# ProPrj_stm32G474_PPO_Display_2026-02-25.net
KiCad netlist of a schematic drawn in EasyEDA Pro
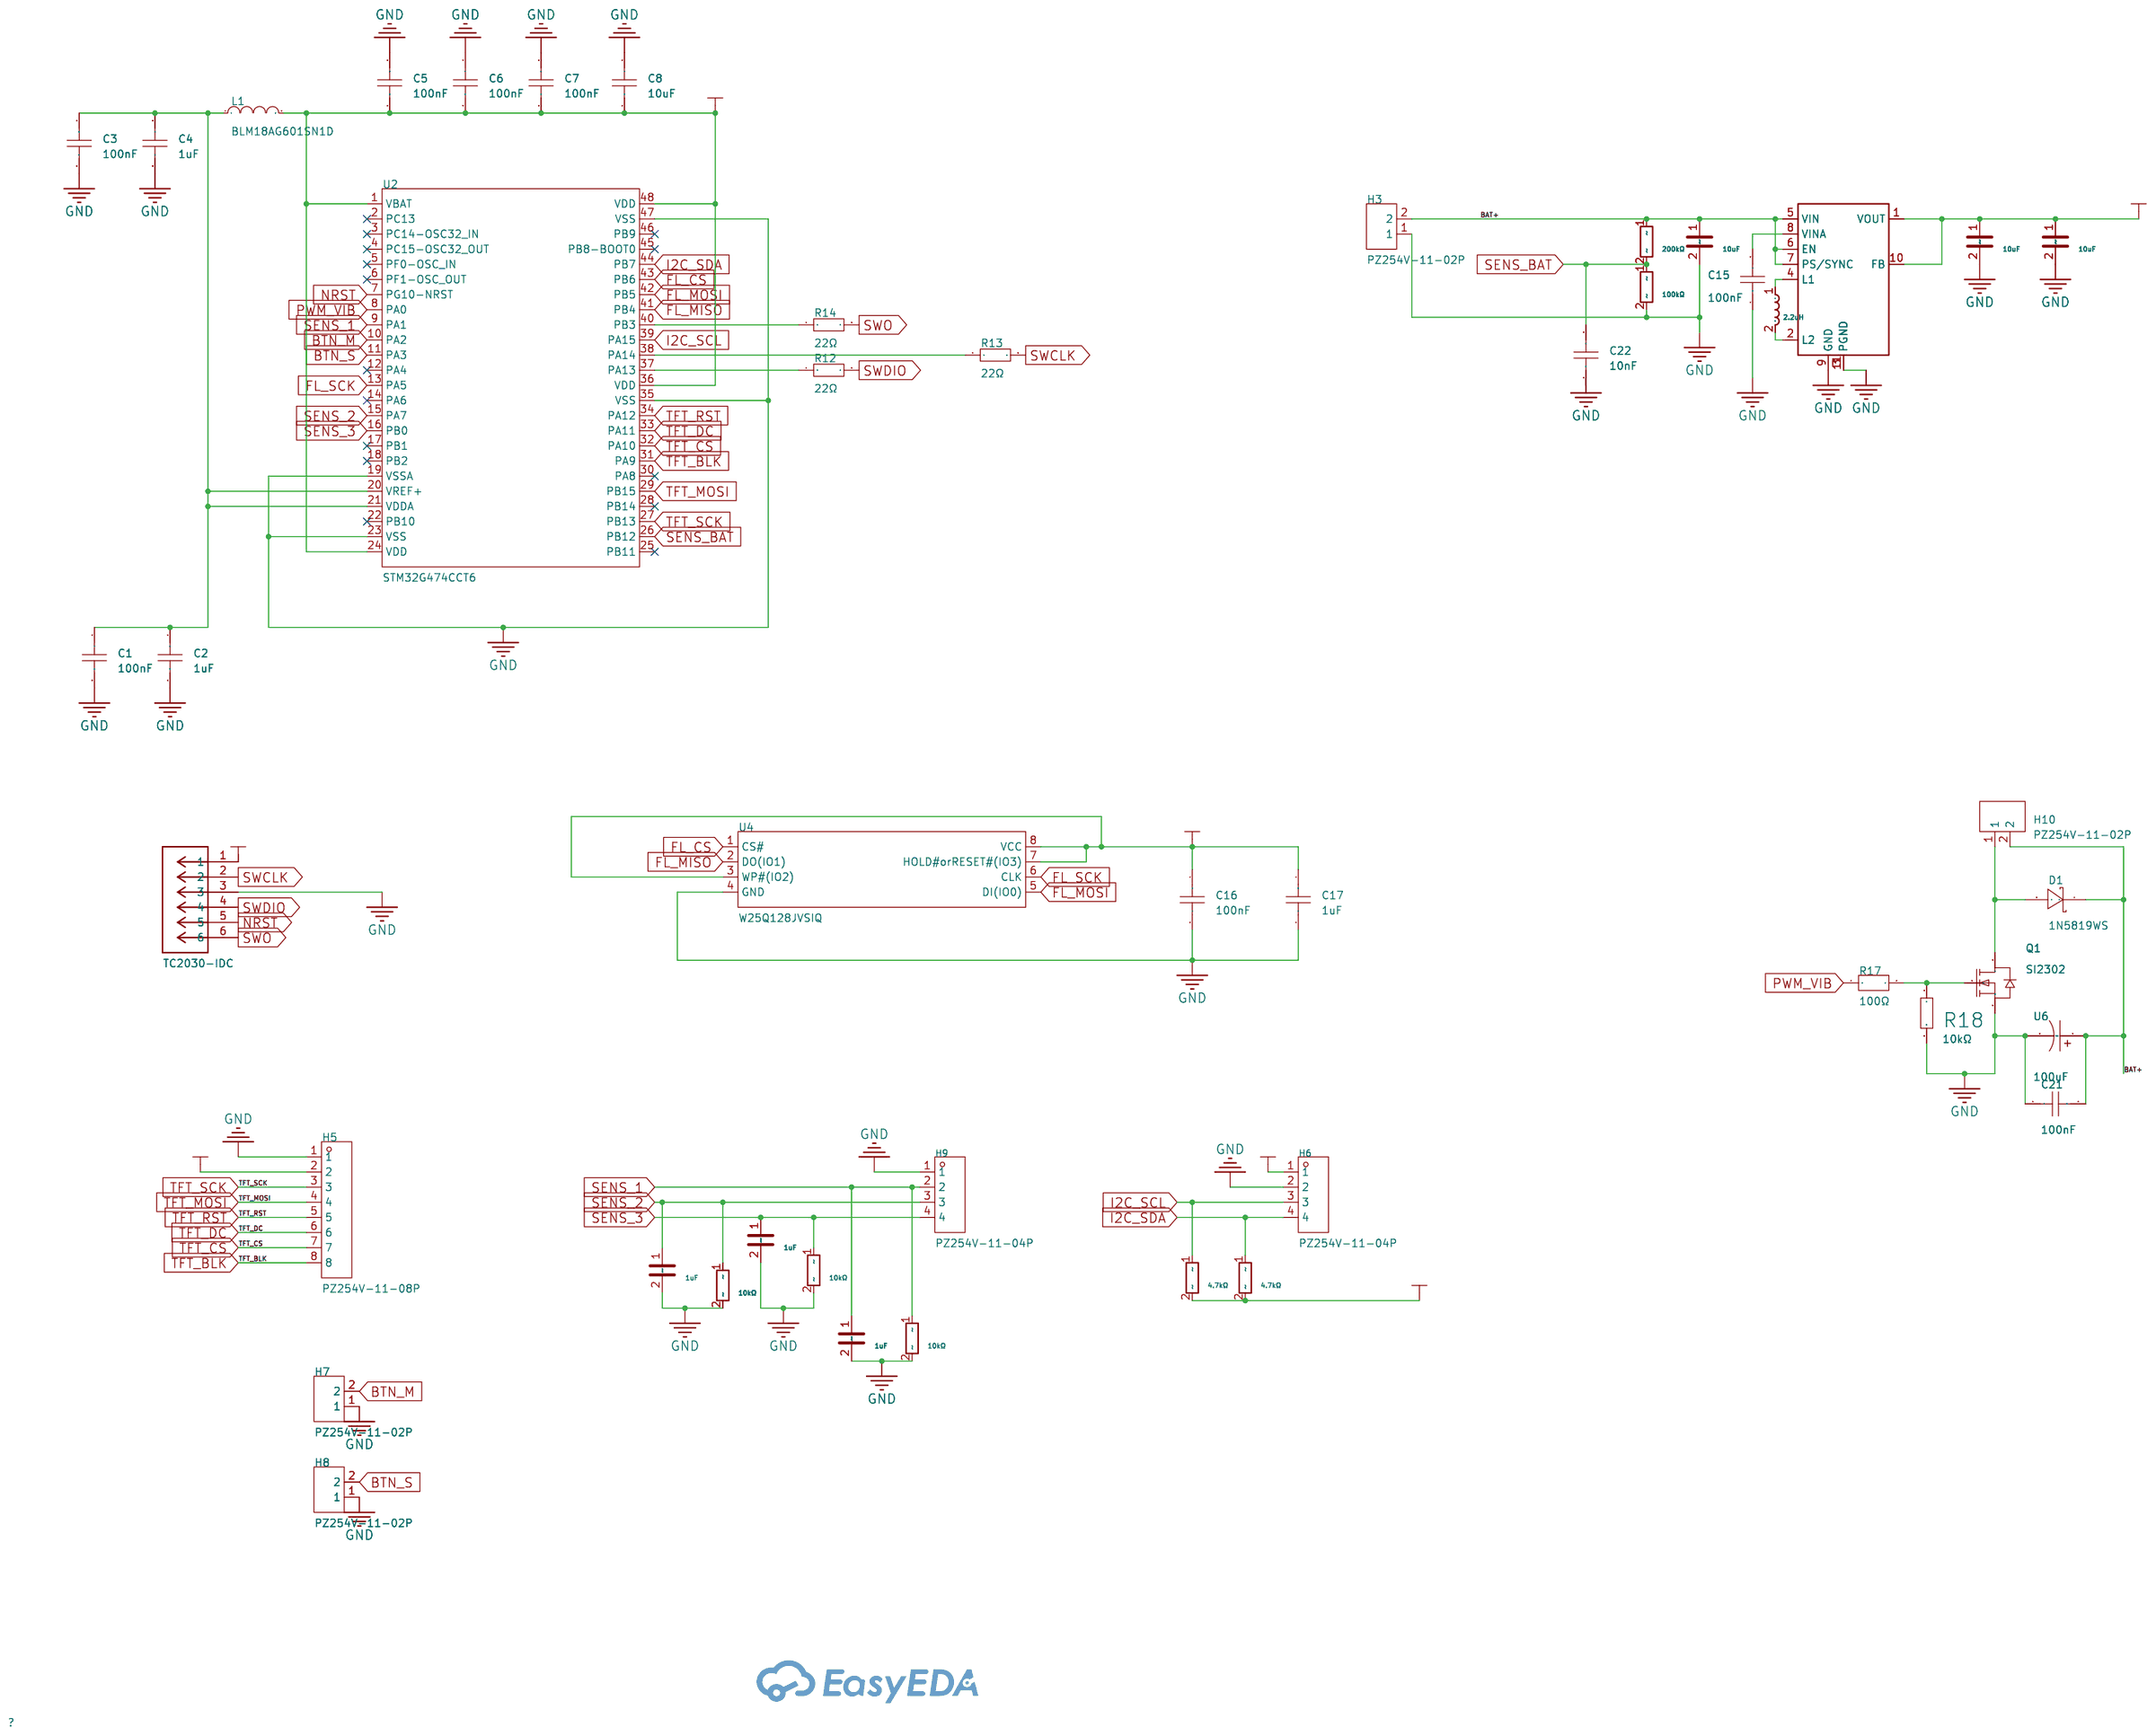
[diagram p0: schematic sheet]

(export (version "E")
  (design (tool "Eeschema 10.0.6"))
  (components
    (comp (ref "C1")
      (value "100nF")
      (footprint "easyedapro:C0603")
      (description "Capacitance:100nF Tolerance:±10% Tolerance:±10% Voltage Rating:50V Temperature Coefficient:X7R")
      (fields
        (field (name "Manufacturer Part") "CC0603KRX7R9BB104")
        (field (name "Manufacturer") "YAGEO(国巨)")
      )
      (libsource (lib "easyedapro") (part "CC0603KRX7R9BB104"))
    )
    (comp (ref "C2")
      (value "1uF")
      (footprint "easyedapro:C0603")
      (description "Capacitance:1uF Tolerance:±10% Tolerance:±10% Voltage Rating:50V Temperature Coefficient:X5R")
      (fields
        (field (name "Manufacturer Part") "CL10A105KB8NNNC")
        (field (name "Manufacturer") "SAMSUNG(三星)")
      )
      (libsource (lib "easyedapro") (part "CL10A105KB8NNNC"))
    )
    (comp (ref "C3")
      (value "100nF")
      (footprint "easyedapro:C0603")
      (description "Capacitance:100nF Tolerance:±10% Tolerance:±10% Voltage Rating:50V Temperature Coefficient:X7R")
      (fields
        (field (name "Manufacturer Part") "CC0603KRX7R9BB104")
        (field (name "Manufacturer") "YAGEO(国巨)")
      )
      (libsource (lib "easyedapro") (part "CC0603KRX7R9BB104"))
    )
    (comp (ref "C4")
      (value "1uF")
      (footprint "easyedapro:C0603")
      (description "Capacitance:1uF Tolerance:±10% Tolerance:±10% Voltage Rating:50V Temperature Coefficient:X5R")
      (fields
        (field (name "Manufacturer Part") "CL10A105KB8NNNC")
        (field (name "Manufacturer") "SAMSUNG(三星)")
      )
      (libsource (lib "easyedapro") (part "CL10A105KB8NNNC"))
    )
    (comp (ref "C5")
      (value "100nF")
      (footprint "easyedapro:C0603")
      (description "Capacitance:100nF Tolerance:±10% Tolerance:±10% Voltage Rating:50V Temperature Coefficient:X7R")
      (fields
        (field (name "Manufacturer Part") "CC0603KRX7R9BB104")
        (field (name "Manufacturer") "YAGEO(国巨)")
      )
      (libsource (lib "easyedapro") (part "CC0603KRX7R9BB104"))
    )
    (comp (ref "C6")
      (value "100nF")
      (footprint "easyedapro:C0603")
      (description "Capacitance:100nF Tolerance:±10% Tolerance:±10% Voltage Rating:50V Temperature Coefficient:X7R")
      (fields
        (field (name "Manufacturer Part") "CC0603KRX7R9BB104")
        (field (name "Manufacturer") "YAGEO(国巨)")
      )
      (libsource (lib "easyedapro") (part "CC0603KRX7R9BB104"))
    )
    (comp (ref "C7")
      (value "100nF")
      (footprint "easyedapro:C0603")
      (description "Capacitance:100nF Tolerance:±10% Tolerance:±10% Voltage Rating:50V Temperature Coefficient:X7R")
      (fields
        (field (name "Manufacturer Part") "CC0603KRX7R9BB104")
        (field (name "Manufacturer") "YAGEO(国巨)")
      )
      (libsource (lib "easyedapro") (part "CC0603KRX7R9BB104"))
    )
    (comp (ref "C8")
      (value "10uF")
      (footprint "easyedapro:C0603")
      (description "Capacitance:10uF Tolerance:±20% Tolerance:±20% Voltage Rating:6.3V Temperature Coefficient:X5R")
      (fields
        (field (name "Manufacturer Part") "CL10A106MQ8NNNC")
        (field (name "Manufacturer") "SAMSUNG(三星)")
      )
      (libsource (lib "easyedapro") (part "CL10A106MQ8NNNC"))
    )
    (comp (ref "C9")
      (value "1uF")
      (footprint "easyedapro:Capacitor_SMD:C_0603_1608Metric")
      (description "Capacitance:1uF Tolerance:±10% Tolerance:±10% Voltage Rating:50V Temperature Coefficient:X7R")
      (fields
        (field (name "Manufacturer Part") "CL10B105KB8NQNC")
        (field (name "Manufacturer") "SAMSUNG(三星)")
      )
      (libsource (lib "easyedapro") (part "Device_C"))
    )
    (comp (ref "C10")
      (value "10uF")
      (footprint "easyedapro:Capacitor_SMD:C_0603_1608Metric")
      (description "Capacitance:10uF Tolerance:±20% Tolerance:±20% Voltage Rating:6.3V Temperature Coefficient:X5R")
      (fields
        (field (name "Manufacturer Part") "CL10A106MQ8NNNC")
        (field (name "Manufacturer") "SAMSUNG(三星)")
      )
      (libsource (lib "easyedapro") (part "Device_C"))
    )
    (comp (ref "C11")
      (value "10uF")
      (footprint "easyedapro:Capacitor_SMD:C_0603_1608Metric")
      (description "Capacitance:10uF Tolerance:±20% Tolerance:±20% Voltage Rating:25V Temperature Coefficient:X5R")
      (fields
        (field (name "Manufacturer Part") "CL10A106MA8NRNC")
        (field (name "Manufacturer") "SAMSUNG(三星)")
      )
      (libsource (lib "easyedapro") (part "Device_C"))
    )
    (comp (ref "C15")
      (value "100nF")
      (footprint "easyedapro:C0603")
      (description "Capacitance:100nF Tolerance:±10% Tolerance:±10% Voltage Rating:50V Temperature Coefficient:X7R")
      (fields
        (field (name "Manufacturer Part") "CC0603KRX7R9BB104")
        (field (name "Manufacturer") "YAGEO(国巨)")
      )
      (libsource (lib "easyedapro") (part "CC0603KRX7R9BB104"))
    )
    (comp (ref "C16")
      (value "100nF")
      (footprint "easyedapro:C0603")
      (description "Capacitance:100nF Tolerance:±10% Tolerance:±10% Voltage Rating:50V Temperature Coefficient:X7R")
      (fields
        (field (name "Manufacturer Part") "CC0603KRX7R9BB104")
        (field (name "Manufacturer") "YAGEO(国巨)")
      )
      (libsource (lib "easyedapro") (part "CC0603KRX7R9BB104"))
    )
    (comp (ref "C17")
      (value "1uF")
      (footprint "easyedapro:C0603")
      (description "Capacitance:1uF Tolerance:±10% Tolerance:±10% Voltage Rating:50V Temperature Coefficient:X5R")
      (fields
        (field (name "Manufacturer Part") "CL10A105KB8NNNC")
        (field (name "Manufacturer") "SAMSUNG(三星)")
      )
      (libsource (lib "easyedapro") (part "CL10A105KB8NNNC"))
    )
    (comp (ref "C18")
      (value "10uF")
      (footprint "easyedapro:Capacitor_SMD:C_0603_1608Metric")
      (description "Capacitance:10uF Tolerance:±20% Tolerance:±20% Voltage Rating:25V Temperature Coefficient:X5R")
      (fields
        (field (name "Manufacturer Part") "CL10A106MA8NRNC")
        (field (name "Manufacturer") "SAMSUNG(三星)")
      )
      (libsource (lib "easyedapro") (part "Device_C"))
    )
    (comp (ref "C19")
      (value "1uF")
      (footprint "easyedapro:Capacitor_SMD:C_0603_1608Metric")
      (description "Capacitance:1uF Tolerance:±10% Tolerance:±10% Voltage Rating:50V Temperature Coefficient:X7R")
      (fields
        (field (name "Manufacturer Part") "CL10B105KB8NQNC")
        (field (name "Manufacturer") "SAMSUNG(三星)")
      )
      (libsource (lib "easyedapro") (part "Device_C"))
    )
    (comp (ref "C20")
      (value "1uF")
      (footprint "easyedapro:Capacitor_SMD:C_0603_1608Metric")
      (description "Capacitance:1uF Tolerance:±10% Tolerance:±10% Voltage Rating:50V Temperature Coefficient:X7R")
      (fields
        (field (name "Manufacturer Part") "CL10B105KB8NQNC")
        (field (name "Manufacturer") "SAMSUNG(三星)")
      )
      (libsource (lib "easyedapro") (part "Device_C"))
    )
    (comp (ref "C21")
      (value "100nF")
      (footprint "easyedapro:C0603")
      (description "Capacitance:100nF Tolerance:±10% Tolerance:±10% Voltage Rating:50V Temperature Coefficient:X7R")
      (fields
        (field (name "Manufacturer Part") "CC0603KRX7R9BB104")
        (field (name "Manufacturer") "YAGEO(国巨)")
      )
      (libsource (lib "easyedapro") (part "CC0603KRX7R9BB104"))
    )
    (comp (ref "C22")
      (value "10nF")
      (footprint "easyedapro:C0603")
      (description "Capacitance:10nF Tolerance:±10% Tolerance:±10% Voltage Rating:50V Temperature Coefficient:X7R")
      (fields
        (field (name "Manufacturer Part") "CL10B103KB8NNNC")
        (field (name "Manufacturer") "SAMSUNG(三星)")
      )
      (libsource (lib "easyedapro") (part "CC0603KRX7R9BB104"))
    )
    (comp (ref "D1")
      (value "1N5819WS")
      (footprint "easyedapro:SOD-323_L1.8-W1.3-LS2.5-RD")
      (fields (field (name "Manufacturer") "Hottech(合科泰)"))
      (libsource (lib "easyedapro") (part "1N5819WS"))
    )
    (comp (ref "H3")
      (value "PZ254V-11-02P")
      (footprint "easyedapro:HDR-TH_2P-P2.54-V-M")
      (fields (field (name "Manufacturer") "XFCN(兴飞)"))
      (libsource (lib "easyedapro") (part "PZ254V-11-02P"))
    )
    (comp (ref "H5")
      (value "PZ254V-11-08P")
      (footprint "easyedapro:HDR-TH_8P-P2.54-V-M")
      (fields (field (name "Manufacturer") "XFCN(兴飞)"))
      (libsource (lib "easyedapro") (part "PZ254V-11-08P"))
    )
    (comp (ref "H6")
      (value "PZ254V-11-04P")
      (footprint "easyedapro:HDR-TH_4P-P2.54-V-M")
      (fields (field (name "Manufacturer") "XFCN(兴飞)"))
      (libsource (lib "easyedapro") (part "PZ254V-11-04P_C2691448"))
    )
    (comp (ref "H7")
      (value "PZ254V-11-02P")
      (footprint "easyedapro:HDR-TH_2P-P2.54-V-M")
      (fields (field (name "Manufacturer") "XFCN(兴飞)"))
      (libsource (lib "easyedapro") (part "PZ254V-11-02P"))
    )
    (comp (ref "H8")
      (value "PZ254V-11-02P")
      (footprint "easyedapro:HDR-TH_2P-P2.54-V-M")
      (fields (field (name "Manufacturer") "XFCN(兴飞)"))
      (libsource (lib "easyedapro") (part "PZ254V-11-02P"))
    )
    (comp (ref "H9")
      (value "PZ254V-11-04P")
      (footprint "easyedapro:HDR-TH_4P-P2.54-V-M")
      (fields (field (name "Manufacturer") "XFCN(兴飞)"))
      (libsource (lib "easyedapro") (part "PZ254V-11-04P_C2691448"))
    )
    (comp (ref "H10")
      (value "PZ254V-11-02P")
      (footprint "easyedapro:HDR-TH_2P-P2.54-V-M")
      (fields (field (name "Manufacturer") "XFCN(兴飞)"))
      (libsource (lib "easyedapro") (part "PZ254V-11-02P"))
    )
    (comp (ref "L1")
      (value "BLM18AG601SN1D")
      (footprint "easyedapro:L0603")
      (fields (field (name "Manufacturer") "muRata(村田)"))
      (libsource (lib "easyedapro") (part "BLM18AG601SN1D"))
    )
    (comp (ref "L2")
      (value "2.2uH")
      (footprint "easyedapro:Inductor_SMD:L_0402_1005Metric")
      (fields (field (name "Manufacturer Part") "LQH3NPN2R2MMEL") (field (name "Manufacturer") "muRata(村田)"))
      (libsource (lib "easyedapro") (part "Device_L"))
    )
    (comp (ref "Q1")
      (value "SI2302")
      (footprint "easyedapro:SOT-23-3_L2.9-W1.3-P1.90-LS2.4-BR")
      (fields (field (name "Manufacturer") "FOSAN(富捷/富信)"))
      (libsource (lib "easyedapro") (part "SI2302_C20628873"))
    )
    (comp (ref "R7")
      (value "200kΩ")
      (footprint "easyedapro:Resistor_SMD:R_0201_0603Metric")
      (fields
        (field (name "Manufacturer Part") "0603WAF2003T5E")
        (field (name "Manufacturer") "UNI-ROYAL(厚声)")
      )
      (libsource (lib "easyedapro") (part "Device_R"))
    )
    (comp (ref "R8")
      (value "100kΩ")
      (footprint "easyedapro:Resistor_SMD:R_0201_0603Metric")
      (fields (field (name "Manufacturer Part") "FRC0603J104 TS") (field (name "Manufacturer") "FOJAN(富捷)"))
      (libsource (lib "easyedapro") (part "Device_R"))
    )
    (comp (ref "R11")
      (value "10kΩ")
      (footprint "easyedapro:Resistor_SMD:R_0201_0603Metric")
      (fields
        (field (name "Manufacturer Part") "0603WAF1002T5E")
        (field (name "Manufacturer") "UNI-ROYAL(厚声)")
      )
      (libsource (lib "easyedapro") (part "Device_R"))
    )
    (comp (ref "R12")
      (value "22Ω")
      (footprint "easyedapro:R0603")
      (fields
        (field (name "Manufacturer Part") "0603WAF220JT5E")
        (field (name "Manufacturer") "UNI-ROYAL(厚声)")
      )
      (libsource (lib "easyedapro") (part "0603WAF220JT5E"))
    )
    (comp (ref "R13")
      (value "22Ω")
      (footprint "easyedapro:R0603")
      (fields
        (field (name "Manufacturer Part") "0603WAF220JT5E")
        (field (name "Manufacturer") "UNI-ROYAL(厚声)")
      )
      (libsource (lib "easyedapro") (part "0603WAF220JT5E"))
    )
    (comp (ref "R14")
      (value "22Ω")
      (footprint "easyedapro:R0603")
      (fields
        (field (name "Manufacturer Part") "0603WAF220JT5E")
        (field (name "Manufacturer") "UNI-ROYAL(厚声)")
      )
      (libsource (lib "easyedapro") (part "0603WAF220JT5E"))
    )
    (comp (ref "R15")
      (value "10kΩ")
      (footprint "easyedapro:Resistor_SMD:R_0201_0603Metric")
      (fields
        (field (name "Manufacturer Part") "0603WAF1002T5E")
        (field (name "Manufacturer") "UNI-ROYAL(厚声)")
      )
      (libsource (lib "easyedapro") (part "Device_R"))
    )
    (comp (ref "R16")
      (value "10kΩ")
      (footprint "easyedapro:Resistor_SMD:R_0201_0603Metric")
      (fields
        (field (name "Manufacturer Part") "0603WAF1002T5E")
        (field (name "Manufacturer") "UNI-ROYAL(厚声)")
      )
      (libsource (lib "easyedapro") (part "Device_R"))
    )
    (comp (ref "R17")
      (value "100Ω")
      (footprint "easyedapro:R0603")
      (fields (field (name "Manufacturer Part") "FRC0603J101 TS") (field (name "Manufacturer") "FOJAN(富捷)"))
      (libsource (lib "easyedapro") (part "FRC0603J101 TS"))
    )
    (comp (ref "R18")
      (value "10kΩ")
      (footprint "easyedapro:R0603")
      (fields
        (field (name "Manufacturer Part") "0603WAF1002T5E")
        (field (name "Manufacturer") "UNI-ROYAL(厚声)")
      )
      (libsource (lib "easyedapro") (part "0603WAF1002T5E"))
    )
    (comp (ref "R19")
      (value "4.7kΩ")
      (footprint "easyedapro:Resistor_SMD:R_0201_0603Metric")
      (fields
        (field (name "Manufacturer Part") "0603WAF4701T5E")
        (field (name "Manufacturer") "UNI-ROYAL(厚声)")
      )
      (libsource (lib "easyedapro") (part "Device_R"))
    )
    (comp (ref "R20")
      (value "4.7kΩ")
      (footprint "easyedapro:Resistor_SMD:R_0201_0603Metric")
      (fields
        (field (name "Manufacturer Part") "0603WAF4701T5E")
        (field (name "Manufacturer") "UNI-ROYAL(厚声)")
      )
      (libsource (lib "easyedapro") (part "Device_R"))
    )
    (comp (ref "U2")
      (value "STM32G474CCT6")
      (footprint "easyedapro:LQFP-48_L7.0-W7.0-P0.50-LS9.0-BL")
      (fields (field (name "Manufacturer") "ST(意法半导体)"))
      (libsource (lib "easyedapro") (part "STM32G474CCT6"))
    )
    (comp (ref "U3")
      (value "TPS63031DSKR")
      (footprint "easyedapro:Package_SON:WSON-10-1EP_2.5x2.5mm_P0.5mm_EP1.2x2mm")
      (fields (field (name "Manufacturer") "TI(德州仪器)"))
      (libsource (lib "easyedapro") (part "Regulator_Switching_TPS63031DSK"))
    )
    (comp (ref "U4")
      (value "W25Q128JVSIQ")
      (footprint "easyedapro:SOIC-8_L5.3-W5.3-P1.27-LS8.0-BL")
      (fields (field (name "Manufacturer") "Winbond(华邦)"))
      (libsource (lib "easyedapro") (part "W25Q128JVSIQ"))
    )
    (comp (ref "U5") (value "TC2030-IDC") (libsource (lib "easyedapro") (part "TC2030-IDC")))
    (comp (ref "U6")
      (value "100uF")
      (footprint "easyedapro:CAP-SMD_BD5.0-L5.3-W5.3-LS6.3-FD")
      (description "Capacitance:100uF Tolerance:±20% Tolerance:±20% Voltage Rating:6.3V Temperature Coefficient:X5R")
      (fields
        (field (name "Manufacturer Part") "CL31A107MQHNNNE")
        (field (name "Manufacturer") "SAMSUNG(三星)")
      )
      (libsource (lib "easyedapro") (part "CK1A101M-CRD54_C3001231"))
    )
  )
  (nets
    (net (code "1") (name "/BAT+") (class "Default")
      (node (ref "C10") (pin "1") (pinfunction "~_1") (pintype "unspecified"))
      (node (ref "C21") (pin "2") (pinfunction "2_2") (pintype "unspecified"))
      (node (ref "D1") (pin "1") (pinfunction "K_1") (pintype "unspecified"))
      (node (ref "H10") (pin "2") (pinfunction "2_2") (pintype "unspecified"))
      (node (ref "H3") (pin "2") (pinfunction "2_2") (pintype "unspecified"))
      (node (ref "R7") (pin "1") (pinfunction "~_1") (pintype "unspecified"))
      (node (ref "U3") (pin "5") (pinfunction "VIN_5") (pintype "unspecified"))
      (node (ref "U3") (pin "6") (pinfunction "EN_6") (pintype "input"))
      (node (ref "U3") (pin "7") (pinfunction "PS/SYNC_7") (pintype "input"))
      (node (ref "U6") (pin "1") (pinfunction "1_1") (pintype "unspecified"))
    )
    (net (code "2") (name "BTN_M") (class "Default")
      (node (ref "H7") (pin "2") (pinfunction "2_2") (pintype "unspecified"))
      (node (ref "U2") (pin "10") (pinfunction "PA2_10") (pintype "unspecified"))
    )
    (net (code "3") (name "BTN_S") (class "Default")
      (node (ref "H8") (pin "2") (pinfunction "2_2") (pintype "unspecified"))
      (node (ref "U2") (pin "11") (pinfunction "PA3_11") (pintype "unspecified"))
    )
    (net (code "4") (name "FL_CS") (class "Default")
      (node (ref "U2") (pin "43") (pinfunction "PB6_43") (pintype "unspecified"))
      (node (ref "U4") (pin "1") (pinfunction "CS#_1") (pintype "unspecified"))
    )
    (net (code "5") (name "FL_MISO") (class "Default")
      (node (ref "U2") (pin "41") (pinfunction "PB4_41") (pintype "unspecified"))
      (node (ref "U4") (pin "2") (pinfunction "DO(IO1)_2") (pintype "unspecified"))
    )
    (net (code "6") (name "FL_MOSI") (class "Default")
      (node (ref "U2") (pin "42") (pinfunction "PB5_42") (pintype "unspecified"))
      (node (ref "U4") (pin "5") (pinfunction "DI(IO0)_5") (pintype "unspecified"))
    )
    (net (code "7") (name "FL_SCK") (class "Default")
      (node (ref "U2") (pin "13") (pinfunction "PA5_13") (pintype "unspecified"))
      (node (ref "U4") (pin "6") (pinfunction "CLK_6") (pintype "unspecified"))
    )
    (net (code "8") (name "GND") (class "Default")
      (node (ref "C1") (pin "2") (pinfunction "2_2") (pintype "unspecified"))
      (node (ref "C10") (pin "2") (pinfunction "~_2") (pintype "unspecified"))
      (node (ref "C11") (pin "2") (pinfunction "~_2") (pintype "unspecified"))
      (node (ref "C15") (pin "1") (pinfunction "1_1") (pintype "unspecified"))
      (node (ref "C16") (pin "2") (pinfunction "2_2") (pintype "unspecified"))
      (node (ref "C17") (pin "2") (pinfunction "2_2") (pintype "unspecified"))
      (node (ref "C18") (pin "2") (pinfunction "~_2") (pintype "unspecified"))
      (node (ref "C19") (pin "2") (pinfunction "~_2") (pintype "unspecified"))
      (node (ref "C2") (pin "2") (pinfunction "2_2") (pintype "unspecified"))
      (node (ref "C20") (pin "2") (pinfunction "~_2") (pintype "unspecified"))
      (node (ref "C21") (pin "1") (pinfunction "1_1") (pintype "unspecified"))
      (node (ref "C22") (pin "1") (pinfunction "1_1") (pintype "unspecified"))
      (node (ref "C3") (pin "2") (pinfunction "2_2") (pintype "unspecified"))
      (node (ref "C4") (pin "2") (pinfunction "2_2") (pintype "unspecified"))
      (node (ref "C5") (pin "1") (pinfunction "1_1") (pintype "unspecified"))
      (node (ref "C6") (pin "1") (pinfunction "1_1") (pintype "unspecified"))
      (node (ref "C7") (pin "1") (pinfunction "1_1") (pintype "unspecified"))
      (node (ref "C8") (pin "1") (pinfunction "1_1") (pintype "unspecified"))
      (node (ref "C9") (pin "2") (pinfunction "~_2") (pintype "unspecified"))
      (node (ref "H3") (pin "1") (pinfunction "1_1") (pintype "unspecified"))
      (node (ref "H5") (pin "1") (pinfunction "1_1") (pintype "unspecified"))
      (node (ref "H6") (pin "2") (pinfunction "2_2") (pintype "input"))
      (node (ref "H7") (pin "1") (pinfunction "1_1") (pintype "unspecified"))
      (node (ref "H8") (pin "1") (pinfunction "1_1") (pintype "unspecified"))
      (node (ref "H9") (pin "1") (pinfunction "1_1") (pintype "input"))
      (node (ref "Q1") (pin "2") (pinfunction "S_2") (pintype "unspecified"))
      (node (ref "R11") (pin "2") (pinfunction "~_2") (pintype "unspecified"))
      (node (ref "R15") (pin "2") (pinfunction "~_2") (pintype "unspecified"))
      (node (ref "R16") (pin "2") (pinfunction "~_2") (pintype "unspecified"))
      (node (ref "R18") (pin "2") (pinfunction "2_2") (pintype "input"))
      (node (ref "R8") (pin "2") (pinfunction "~_2") (pintype "unspecified"))
      (node (ref "U2") (pin "19") (pinfunction "VSSA_19") (pintype "unspecified"))
      (node (ref "U2") (pin "23") (pinfunction "VSS_23") (pintype "unspecified"))
      (node (ref "U2") (pin "35") (pinfunction "VSS_35") (pintype "unspecified"))
      (node (ref "U2") (pin "47") (pinfunction "VSS_47") (pintype "unspecified"))
      (node (ref "U3") (pin "11") (pinfunction "PGND_11") (pintype "unspecified"))
      (node (ref "U3") (pin "3") (pinfunction "PGND_3") (pintype "unspecified"))
      (node (ref "U3") (pin "9") (pinfunction "GND_9") (pintype "unspecified"))
      (node (ref "U4") (pin "4") (pinfunction "GND_4") (pintype "unspecified"))
      (node (ref "U5") (pin "3") (pinfunction "3_3") (pintype "unspecified"))
      (node (ref "U6") (pin "2") (pinfunction "2_2") (pintype "unspecified"))
    )
    (net (code "9") (name "I2C_SCL") (class "Default")
      (node (ref "H6") (pin "3") (pinfunction "3_3") (pintype "input"))
      (node (ref "R19") (pin "1") (pinfunction "~_1") (pintype "unspecified"))
      (node (ref "U2") (pin "39") (pinfunction "PA15_39") (pintype "unspecified"))
    )
    (net (code "10") (name "I2C_SDA") (class "Default")
      (node (ref "H6") (pin "4") (pinfunction "4_4") (pintype "input"))
      (node (ref "R20") (pin "1") (pinfunction "~_1") (pintype "unspecified"))
      (node (ref "U2") (pin "44") (pinfunction "PB7_44") (pintype "unspecified"))
    )
    (net (code "11") (name "NRST") (class "Default")
      (node (ref "U2") (pin "7") (pinfunction "PG10-NRST_7") (pintype "unspecified"))
      (node (ref "U5") (pin "5") (pinfunction "5_5") (pintype "unspecified"))
    )
    (net (code "12") (name "Net-(D1-A)") (class "Default")
      (node (ref "D1") (pin "2") (pinfunction "A_2") (pintype "unspecified"))
      (node (ref "H10") (pin "1") (pinfunction "1_1") (pintype "unspecified"))
      (node (ref "Q1") (pin "3") (pinfunction "D_3") (pintype "unspecified"))
    )
    (net (code "13") (name "Net-(Q1-G)") (class "Default")
      (node (ref "Q1") (pin "1") (pinfunction "G_1") (pintype "unspecified"))
      (node (ref "R17") (pin "2") (pinfunction "2_2") (pintype "unspecified"))
      (node (ref "R18") (pin "1") (pinfunction "1_1") (pintype "input"))
    )
    (net (code "14") (name "Net-(U2-PA13)") (class "Default")
      (node (ref "R12") (pin "1") (pinfunction "1_1") (pintype "input"))
      (node (ref "U2") (pin "37") (pinfunction "PA13_37") (pintype "unspecified"))
    )
    (net (code "15") (name "Net-(U2-PA14)") (class "Default")
      (node (ref "R13") (pin "1") (pinfunction "1_1") (pintype "input"))
      (node (ref "U2") (pin "38") (pinfunction "PA14_38") (pintype "unspecified"))
    )
    (net (code "16") (name "Net-(U2-PB3)") (class "Default")
      (node (ref "R14") (pin "1") (pinfunction "1_1") (pintype "input"))
      (node (ref "U2") (pin "40") (pinfunction "PB3_40") (pintype "unspecified"))
    )
    (net (code "17") (name "Net-(U2-VDDA)") (class "Default")
      (node (ref "C1") (pin "1") (pinfunction "1_1") (pintype "unspecified"))
      (node (ref "C2") (pin "1") (pinfunction "1_1") (pintype "unspecified"))
      (node (ref "C3") (pin "1") (pinfunction "1_1") (pintype "unspecified"))
      (node (ref "C4") (pin "1") (pinfunction "1_1") (pintype "unspecified"))
      (node (ref "L1") (pin "1") (pinfunction "1_1") (pintype "unspecified"))
      (node (ref "U2") (pin "20") (pinfunction "VREF+_20") (pintype "unspecified"))
      (node (ref "U2") (pin "21") (pinfunction "VDDA_21") (pintype "unspecified"))
    )
    (net (code "18") (name "Net-(U3-L1)") (class "Default")
      (node (ref "L2") (pin "1") (pinfunction "1_1") (pintype "unspecified"))
      (node (ref "U3") (pin "4") (pinfunction "L1_4") (pintype "input"))
    )
    (net (code "19") (name "Net-(U3-L2)") (class "Default")
      (node (ref "L2") (pin "2") (pinfunction "2_2") (pintype "unspecified"))
      (node (ref "U3") (pin "2") (pinfunction "L2_2") (pintype "input"))
    )
    (net (code "20") (name "Net-(U3-VINA)") (class "Default")
      (node (ref "C15") (pin "2") (pinfunction "2_2") (pintype "unspecified"))
      (node (ref "U3") (pin "8") (pinfunction "VINA_8") (pintype "unspecified"))
    )
    (net (code "21") (name "PWM_VIB") (class "Default")
      (node (ref "R17") (pin "1") (pinfunction "1_1") (pintype "unspecified"))
      (node (ref "U2") (pin "8") (pinfunction "PA0_8") (pintype "unspecified"))
    )
    (net (code "22") (name "SENS_1") (class "Default")
      (node (ref "C9") (pin "1") (pinfunction "~_1") (pintype "unspecified"))
      (node (ref "H9") (pin "2") (pinfunction "2_2") (pintype "input"))
      (node (ref "R16") (pin "1") (pinfunction "~_1") (pintype "unspecified"))
      (node (ref "U2") (pin "9") (pinfunction "PA1_9") (pintype "unspecified"))
    )
    (net (code "23") (name "SENS_2") (class "Default")
      (node (ref "C19") (pin "1") (pinfunction "~_1") (pintype "unspecified"))
      (node (ref "H9") (pin "3") (pinfunction "3_3") (pintype "input"))
      (node (ref "R11") (pin "1") (pinfunction "~_1") (pintype "unspecified"))
      (node (ref "U2") (pin "15") (pinfunction "PA7_15") (pintype "unspecified"))
    )
    (net (code "24") (name "SENS_3") (class "Default")
      (node (ref "C20") (pin "1") (pinfunction "~_1") (pintype "unspecified"))
      (node (ref "H9") (pin "4") (pinfunction "4_4") (pintype "input"))
      (node (ref "R15") (pin "1") (pinfunction "~_1") (pintype "unspecified"))
      (node (ref "U2") (pin "16") (pinfunction "PB0_16") (pintype "unspecified"))
    )
    (net (code "25") (name "SENS_BAT") (class "Default")
      (node (ref "C22") (pin "2") (pinfunction "2_2") (pintype "unspecified"))
      (node (ref "R7") (pin "2") (pinfunction "~_2") (pintype "unspecified"))
      (node (ref "R8") (pin "1") (pinfunction "~_1") (pintype "unspecified"))
      (node (ref "U2") (pin "26") (pinfunction "PB12_26") (pintype "unspecified"))
    )
    (net (code "26") (name "SWCLK") (class "Default")
      (node (ref "R13") (pin "2") (pinfunction "2_2") (pintype "input"))
      (node (ref "U5") (pin "2") (pinfunction "2_2") (pintype "unspecified"))
    )
    (net (code "27") (name "SWDIO") (class "Default")
      (node (ref "R12") (pin "2") (pinfunction "2_2") (pintype "input"))
      (node (ref "U5") (pin "4") (pinfunction "4_4") (pintype "unspecified"))
    )
    (net (code "28") (name "SWO") (class "Default")
      (node (ref "R14") (pin "2") (pinfunction "2_2") (pintype "input"))
      (node (ref "U5") (pin "6") (pinfunction "6_6") (pintype "unspecified"))
    )
    (net (code "29") (name "TFT_BLK") (class "Default")
      (node (ref "H5") (pin "8") (pinfunction "8_8") (pintype "unspecified"))
      (node (ref "U2") (pin "31") (pinfunction "PA9_31") (pintype "unspecified"))
    )
    (net (code "30") (name "TFT_CS") (class "Default")
      (node (ref "H5") (pin "7") (pinfunction "7_7") (pintype "unspecified"))
      (node (ref "U2") (pin "32") (pinfunction "PA10_32") (pintype "unspecified"))
    )
    (net (code "31") (name "TFT_DC") (class "Default")
      (node (ref "H5") (pin "6") (pinfunction "6_6") (pintype "unspecified"))
      (node (ref "U2") (pin "33") (pinfunction "PA11_33") (pintype "unspecified"))
    )
    (net (code "32") (name "TFT_MOSI") (class "Default")
      (node (ref "H5") (pin "4") (pinfunction "4_4") (pintype "unspecified"))
      (node (ref "U2") (pin "29") (pinfunction "PB15_29") (pintype "unspecified"))
    )
    (net (code "33") (name "TFT_RST") (class "Default")
      (node (ref "H5") (pin "5") (pinfunction "5_5") (pintype "unspecified"))
      (node (ref "U2") (pin "34") (pinfunction "PA12_34") (pintype "unspecified"))
    )
    (net (code "34") (name "TFT_SCK") (class "Default")
      (node (ref "H5") (pin "3") (pinfunction "3_3") (pintype "unspecified"))
      (node (ref "U2") (pin "27") (pinfunction "PB13_27") (pintype "unspecified"))
    )
    (net (code "35") (name "VDD") (class "Default")
      (node (ref "C11") (pin "1") (pinfunction "~_1") (pintype "unspecified"))
      (node (ref "C16") (pin "1") (pinfunction "1_1") (pintype "unspecified"))
      (node (ref "C17") (pin "1") (pinfunction "1_1") (pintype "unspecified"))
      (node (ref "C18") (pin "1") (pinfunction "~_1") (pintype "unspecified"))
      (node (ref "C5") (pin "2") (pinfunction "2_2") (pintype "unspecified"))
      (node (ref "C6") (pin "2") (pinfunction "2_2") (pintype "unspecified"))
      (node (ref "C7") (pin "2") (pinfunction "2_2") (pintype "unspecified"))
      (node (ref "C8") (pin "2") (pinfunction "2_2") (pintype "unspecified"))
      (node (ref "H5") (pin "2") (pinfunction "2_2") (pintype "unspecified"))
      (node (ref "H6") (pin "1") (pinfunction "1_1") (pintype "input"))
      (node (ref "L1") (pin "2") (pinfunction "2_2") (pintype "unspecified"))
      (node (ref "R19") (pin "2") (pinfunction "~_2") (pintype "unspecified"))
      (node (ref "R20") (pin "2") (pinfunction "~_2") (pintype "unspecified"))
      (node (ref "U2") (pin "1") (pinfunction "VBAT_1") (pintype "unspecified"))
      (node (ref "U2") (pin "24") (pinfunction "VDD_24") (pintype "unspecified"))
      (node (ref "U2") (pin "36") (pinfunction "VDD_36") (pintype "unspecified"))
      (node (ref "U2") (pin "48") (pinfunction "VDD_48") (pintype "unspecified"))
      (node (ref "U3") (pin "1") (pinfunction "VOUT_1") (pintype "unspecified"))
      (node (ref "U3") (pin "10") (pinfunction "FB_10") (pintype "input"))
      (node (ref "U4") (pin "3") (pinfunction "WP#(IO2)_3") (pintype "unspecified"))
      (node (ref "U4") (pin "7") (pinfunction "HOLD#orRESET#(IO3)_7") (pintype "unspecified"))
      (node (ref "U4") (pin "8") (pinfunction "VCC_8") (pintype "unspecified"))
      (node (ref "U5") (pin "1") (pinfunction "1_1") (pintype "unspecified"))
    )
    (net (code "36") (name "unconnected-(U2-PA4-Pad12)") (class "Default")
      (node (ref "U2") (pin "12") (pinfunction "PA4_12") (pintype "unspecified+no_connect"))
    )
    (net (code "37") (name "unconnected-(U2-PA6-Pad14)") (class "Default")
      (node (ref "U2") (pin "14") (pinfunction "PA6_14") (pintype "unspecified+no_connect"))
    )
    (net (code "38") (name "unconnected-(U2-PA8-Pad30)") (class "Default")
      (node (ref "U2") (pin "30") (pinfunction "PA8_30") (pintype "unspecified+no_connect"))
    )
    (net (code "39") (name "unconnected-(U2-PB1-Pad17)") (class "Default")
      (node (ref "U2") (pin "17") (pinfunction "PB1_17") (pintype "unspecified+no_connect"))
    )
    (net (code "40") (name "unconnected-(U2-PB2-Pad18)") (class "Default")
      (node (ref "U2") (pin "18") (pinfunction "PB2_18") (pintype "unspecified+no_connect"))
    )
    (net (code "41") (name "unconnected-(U2-PB8-BOOT0-Pad45)") (class "Default")
      (node (ref "U2") (pin "45") (pinfunction "PB8-BOOT0_45") (pintype "unspecified+no_connect"))
    )
    (net (code "42") (name "unconnected-(U2-PB9-Pad46)") (class "Default")
      (node (ref "U2") (pin "46") (pinfunction "PB9_46") (pintype "unspecified+no_connect"))
    )
    (net (code "43") (name "unconnected-(U2-PB10-Pad22)") (class "Default")
      (node (ref "U2") (pin "22") (pinfunction "PB10_22") (pintype "unspecified+no_connect"))
    )
    (net (code "44") (name "unconnected-(U2-PB11-Pad25)") (class "Default")
      (node (ref "U2") (pin "25") (pinfunction "PB11_25") (pintype "unspecified+no_connect"))
    )
    (net (code "45") (name "unconnected-(U2-PB14-Pad28)") (class "Default")
      (node (ref "U2") (pin "28") (pinfunction "PB14_28") (pintype "unspecified+no_connect"))
    )
    (net (code "46") (name "unconnected-(U2-PC13-Pad2)") (class "Default")
      (node (ref "U2") (pin "2") (pinfunction "PC13_2") (pintype "unspecified+no_connect"))
    )
    (net (code "47") (name "unconnected-(U2-PC14-OSC32_IN-Pad3)") (class "Default")
      (node (ref "U2") (pin "3") (pinfunction "PC14-OSC32_IN_3") (pintype "unspecified+no_connect"))
    )
    (net (code "48") (name "unconnected-(U2-PC15-OSC32_OUT-Pad4)") (class "Default")
      (node (ref "U2") (pin "4") (pinfunction "PC15-OSC32_OUT_4") (pintype "unspecified+no_connect"))
    )
    (net (code "49") (name "unconnected-(U2-PF0-OSC_IN-Pad5)") (class "Default")
      (node (ref "U2") (pin "5") (pinfunction "PF0-OSC_IN_5") (pintype "unspecified+no_connect"))
    )
    (net (code "50") (name "unconnected-(U2-PF1-OSC_OUT-Pad6)") (class "Default")
      (node (ref "U2") (pin "6") (pinfunction "PF1-OSC_OUT_6") (pintype "unspecified+no_connect"))
    )
  )
)
